# VCO.net
KiCad netlist of a schematic drawn in Altium Designer
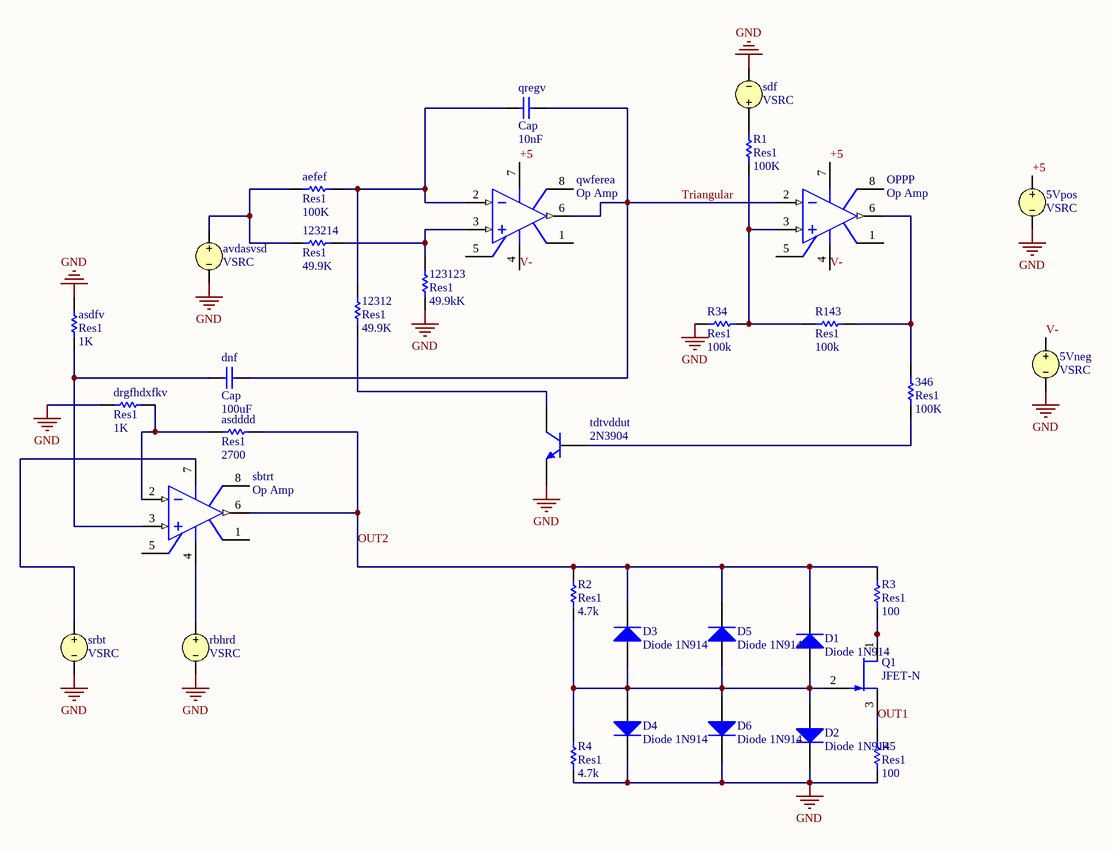
[diagram p0: VCO.SchDoc]

(export (version "E")
  (design (tool "Eeschema 10.0.6"))
  (components
    (comp (ref "5Vneg")
      (value "VSRC")
      (description "Voltage Source")
      (fields (field (name "PUBLISHER") "Altium Limited"))
      (libsource (lib "Simulation Sources") (part "VSRC"))
    )
    (comp (ref "5Vpos")
      (value "VSRC")
      (description "Voltage Source")
      (fields (field (name "PUBLISHER") "Altium Limited"))
      (libsource (lib "Simulation Sources") (part "VSRC"))
    )
    (comp (ref "346")
      (value "Res1")
      (footprint "AXIAL-0.3")
      (description "Resistor")
      (fields (field (name "ALTIUM_VALUE") "100K") (field (name "PUBLISHER") "Altium Limited"))
      (libsource (lib "Miscellaneous Devices") (part "Res1"))
    )
    (comp (ref "12312")
      (value "Res1")
      (footprint "AXIAL-0.3")
      (description "Resistor")
      (fields (field (name "ALTIUM_VALUE") "49.9K") (field (name "PUBLISHER") "Altium Limited"))
      (libsource (lib "Miscellaneous Devices") (part "Res1"))
    )
    (comp (ref "123123")
      (value "Res1")
      (footprint "AXIAL-0.3")
      (description "Resistor")
      (fields (field (name "ALTIUM_VALUE") "49.9kK") (field (name "PUBLISHER") "Altium Limited"))
      (libsource (lib "Miscellaneous Devices") (part "Res1"))
    )
    (comp (ref "123214")
      (value "Res1")
      (footprint "AXIAL-0.3")
      (description "Resistor")
      (fields (field (name "ALTIUM_VALUE") "49.9K") (field (name "PUBLISHER") "Altium Limited"))
      (libsource (lib "Miscellaneous Devices") (part "Res1"))
    )
    (comp (ref "aefef")
      (value "Res1")
      (footprint "AXIAL-0.3")
      (description "Resistor")
      (fields (field (name "ALTIUM_VALUE") "100K") (field (name "PUBLISHER") "Altium Limited"))
      (libsource (lib "Miscellaneous Devices") (part "Res1"))
    )
    (comp (ref "asdddd")
      (value "Res1")
      (footprint "AXIAL-0.3")
      (description "Resistor")
      (fields (field (name "ALTIUM_VALUE") "2700") (field (name "PUBLISHER") "Altium Limited"))
      (libsource (lib "Miscellaneous Devices") (part "Res1"))
    )
    (comp (ref "asdfv")
      (value "Res1")
      (footprint "AXIAL-0.3")
      (description "Resistor")
      (fields (field (name "ALTIUM_VALUE") "1K") (field (name "PUBLISHER") "Altium Limited"))
      (libsource (lib "Miscellaneous Devices") (part "Res1"))
    )
    (comp (ref "avdasvsd")
      (value "VSRC")
      (description "Voltage Source")
      (fields (field (name "PUBLISHER") "Altium Limited"))
      (libsource (lib "Simulation Sources") (part "VSRC"))
    )
    (comp (ref "D1")
      (value "Diode 1N914")
      (footprint "DO-35")
      (description "High Conductance Fast Diode")
      (fields (field (name "PUBLISHER") "Altium Limited"))
      (libsource (lib "Miscellaneous Devices") (part "Diode 1N914"))
    )
    (comp (ref "D2")
      (value "Diode 1N914")
      (footprint "DO-35")
      (description "High Conductance Fast Diode")
      (fields (field (name "PUBLISHER") "Altium Limited"))
      (libsource (lib "Miscellaneous Devices") (part "Diode 1N914"))
    )
    (comp (ref "D3")
      (value "Diode 1N914")
      (footprint "DO-35")
      (description "High Conductance Fast Diode")
      (fields (field (name "PUBLISHER") "Altium Limited"))
      (libsource (lib "Miscellaneous Devices") (part "Diode 1N914"))
    )
    (comp (ref "D4")
      (value "Diode 1N914")
      (footprint "DO-35")
      (description "High Conductance Fast Diode")
      (fields (field (name "PUBLISHER") "Altium Limited"))
      (libsource (lib "Miscellaneous Devices") (part "Diode 1N914"))
    )
    (comp (ref "D5")
      (value "Diode 1N914")
      (footprint "DO-35")
      (description "High Conductance Fast Diode")
      (fields (field (name "PUBLISHER") "Altium Limited"))
      (libsource (lib "Miscellaneous Devices") (part "Diode 1N914"))
    )
    (comp (ref "D6")
      (value "Diode 1N914")
      (footprint "DO-35")
      (description "High Conductance Fast Diode")
      (fields (field (name "PUBLISHER") "Altium Limited"))
      (libsource (lib "Miscellaneous Devices") (part "Diode 1N914"))
    )
    (comp (ref "dnf")
      (value "Cap")
      (footprint "RAD-0.3")
      (description "Capacitor")
      (fields (field (name "ALTIUM_VALUE") "100uF") (field (name "PUBLISHER") "Altium Limited"))
      (libsource (lib "Miscellaneous Devices") (part "Cap"))
    )
    (comp (ref "drgfhdxfkv")
      (value "Res1")
      (footprint "AXIAL-0.3")
      (description "Resistor")
      (fields (field (name "ALTIUM_VALUE") "1K") (field (name "PUBLISHER") "Altium Limited"))
      (libsource (lib "Miscellaneous Devices") (part "Res1"))
    )
    (comp (ref "OPPP")
      (value "Op Amp")
      (footprint "H-08A")
      (description "FET Operational Amplifier")
      (fields (field (name "PUBLISHER") "Altium Limited"))
      (libsource (lib "Miscellaneous Devices") (part "Op Amp"))
    )
    (comp (ref "Q1")
      (value "JFET-N")
      (footprint "TO-254-AA")
      (description "N-Channel JFET")
      (fields (field (name "PUBLISHER") "Altium Limited"))
      (libsource (lib "Miscellaneous Devices") (part "JFET-N"))
    )
    (comp (ref "qregv")
      (value "Cap")
      (footprint "RAD-0.3")
      (description "Capacitor")
      (fields (field (name "ALTIUM_VALUE") "10nF") (field (name "PUBLISHER") "Altium Limited"))
      (libsource (lib "Miscellaneous Devices") (part "Cap"))
    )
    (comp (ref "qwferea")
      (value "Op Amp")
      (footprint "H-08A")
      (description "FET Operational Amplifier")
      (fields (field (name "PUBLISHER") "Altium Limited"))
      (libsource (lib "Miscellaneous Devices") (part "Op Amp"))
    )
    (comp (ref "R1")
      (value "Res1")
      (footprint "AXIAL-0.3")
      (description "Resistor")
      (fields (field (name "ALTIUM_VALUE") "100K") (field (name "PUBLISHER") "Altium Limited"))
      (libsource (lib "Miscellaneous Devices") (part "Res1"))
    )
    (comp (ref "R2")
      (value "Res1")
      (footprint "AXIAL-0.3")
      (description "Resistor")
      (fields (field (name "ALTIUM_VALUE") "4.7k") (field (name "PUBLISHER") "Altium Limited"))
      (libsource (lib "Miscellaneous Devices") (part "Res1"))
    )
    (comp (ref "R3")
      (value "Res1")
      (footprint "AXIAL-0.3")
      (description "Resistor")
      (fields (field (name "ALTIUM_VALUE") "100") (field (name "PUBLISHER") "Altium Limited"))
      (libsource (lib "Miscellaneous Devices") (part "Res1"))
    )
    (comp (ref "R4")
      (value "Res1")
      (footprint "AXIAL-0.3")
      (description "Resistor")
      (fields (field (name "ALTIUM_VALUE") "4.7k") (field (name "PUBLISHER") "Altium Limited"))
      (libsource (lib "Miscellaneous Devices") (part "Res1"))
    )
    (comp (ref "R5")
      (value "Res1")
      (footprint "AXIAL-0.3")
      (description "Resistor")
      (fields (field (name "ALTIUM_VALUE") "100") (field (name "PUBLISHER") "Altium Limited"))
      (libsource (lib "Miscellaneous Devices") (part "Res1"))
    )
    (comp (ref "R34")
      (value "Res1")
      (footprint "AXIAL-0.3")
      (description "Resistor")
      (fields (field (name "ALTIUM_VALUE") "100k") (field (name "PUBLISHER") "Altium Limited"))
      (libsource (lib "Miscellaneous Devices") (part "Res1"))
    )
    (comp (ref "R143")
      (value "Res1")
      (footprint "AXIAL-0.3")
      (description "Resistor")
      (fields (field (name "ALTIUM_VALUE") "100k") (field (name "PUBLISHER") "Altium Limited"))
      (libsource (lib "Miscellaneous Devices") (part "Res1"))
    )
    (comp (ref "rbhrd")
      (value "VSRC")
      (description "Voltage Source")
      (fields (field (name "PUBLISHER") "Altium Limited"))
      (libsource (lib "Simulation Sources") (part "VSRC"))
    )
    (comp (ref "sbtrt")
      (value "Op Amp")
      (footprint "H-08A")
      (description "FET Operational Amplifier")
      (fields (field (name "PUBLISHER") "Altium Limited"))
      (libsource (lib "Miscellaneous Devices") (part "Op Amp"))
    )
    (comp (ref "sdf")
      (value "VSRC")
      (description "Voltage Source")
      (fields (field (name "PUBLISHER") "Altium Limited"))
      (libsource (lib "Simulation Sources") (part "VSRC"))
    )
    (comp (ref "srbt")
      (value "VSRC")
      (description "Voltage Source")
      (fields (field (name "PUBLISHER") "Altium Limited"))
      (libsource (lib "Simulation Sources") (part "VSRC"))
    )
    (comp (ref "tdtvddut")
      (value "2N3904")
      (footprint "TO-92A")
      (description "NPN General Purpose Amplifier")
      (fields (field (name "PUBLISHER") "Altium Limited"))
      (libsource (lib "Miscellaneous Devices") (part "2N3904"))
    )
  )
  (nets
    (net (code "1") (name "/+5") (class "Default")
      (node (ref "5Vpos") (pin "1") (pinfunction "1_1") (pintype "passive"))
      (node (ref "OPPP") (pin "7") (pinfunction "V+_7") (pintype "power_in"))
      (node (ref "qwferea") (pin "7") (pinfunction "V+_7") (pintype "power_in"))
    )
    (net (code "2") (name "/OUT1") (class "Default")
      (node (ref "Q1") (pin "3") (pinfunction "S_3") (pintype "passive"))
      (node (ref "R5") (pin "2") (pinfunction "2_2") (pintype "passive"))
    )
    (net (code "3") (name "/OUT2") (class "Default")
      (node (ref "D1") (pin "2") (pinfunction "K_2") (pintype "passive"))
      (node (ref "D3") (pin "2") (pinfunction "K_2") (pintype "passive"))
      (node (ref "D5") (pin "2") (pinfunction "K_2") (pintype "passive"))
      (node (ref "R2") (pin "2") (pinfunction "2_2") (pintype "passive"))
      (node (ref "R3") (pin "2") (pinfunction "2_2") (pintype "passive"))
      (node (ref "asdddd") (pin "2") (pinfunction "2_2") (pintype "passive"))
      (node (ref "sbtrt") (pin "6") (pinfunction "OUT_6") (pintype "output"))
    )
    (net (code "4") (name "/Triangular") (class "Default")
      (node (ref "OPPP") (pin "2") (pinfunction "IN-_2") (pintype "input"))
      (node (ref "dnf") (pin "2") (pinfunction "2_2") (pintype "passive"))
      (node (ref "qregv") (pin "2") (pinfunction "2_2") (pintype "passive"))
      (node (ref "qwferea") (pin "6") (pinfunction "OUT_6") (pintype "output"))
    )
    (net (code "5") (name "/V-") (class "Default")
      (node (ref "5Vneg") (pin "1") (pinfunction "1_1") (pintype "passive"))
      (node (ref "OPPP") (pin "4") (pinfunction "V-_4") (pintype "power_in"))
      (node (ref "qwferea") (pin "4") (pinfunction "V-_4") (pintype "power_in"))
    )
    (net (code "6") (name "GND") (class "Default")
      (node (ref "123123") (pin "1") (pinfunction "1_1") (pintype "passive"))
      (node (ref "5Vneg") (pin "2") (pinfunction "2_2") (pintype "passive"))
      (node (ref "5Vpos") (pin "2") (pinfunction "2_2") (pintype "passive"))
      (node (ref "D2") (pin "2") (pinfunction "K_2") (pintype "passive"))
      (node (ref "D4") (pin "2") (pinfunction "K_2") (pintype "passive"))
      (node (ref "D6") (pin "2") (pinfunction "K_2") (pintype "passive"))
      (node (ref "R34") (pin "1") (pinfunction "1_1") (pintype "passive"))
      (node (ref "R4") (pin "1") (pinfunction "1_1") (pintype "passive"))
      (node (ref "R5") (pin "1") (pinfunction "1_1") (pintype "passive"))
      (node (ref "asdfv") (pin "2") (pinfunction "2_2") (pintype "passive"))
      (node (ref "avdasvsd") (pin "2") (pinfunction "2_2") (pintype "passive"))
      (node (ref "drgfhdxfkv") (pin "2") (pinfunction "2_2") (pintype "passive"))
      (node (ref "rbhrd") (pin "2") (pinfunction "2_2") (pintype "passive"))
      (node (ref "sdf") (pin "2") (pinfunction "2_2") (pintype "passive"))
      (node (ref "srbt") (pin "2") (pinfunction "2_2") (pintype "passive"))
      (node (ref "tdtvddut") (pin "1") (pinfunction "E_1") (pintype "passive"))
    )
    (net (code "7") (name "Net-(123214-Pad1)") (class "Default")
      (node (ref "123214") (pin "1") (pinfunction "1_1") (pintype "passive"))
      (node (ref "aefef") (pin "1") (pinfunction "1_1") (pintype "passive"))
      (node (ref "avdasvsd") (pin "1") (pinfunction "1_1") (pintype "passive"))
    )
    (net (code "8") (name "Net-(D1-A)") (class "Default")
      (node (ref "D1") (pin "1") (pinfunction "A_1") (pintype "passive"))
      (node (ref "D2") (pin "1") (pinfunction "A_1") (pintype "passive"))
      (node (ref "D3") (pin "1") (pinfunction "A_1") (pintype "passive"))
      (node (ref "D4") (pin "1") (pinfunction "A_1") (pintype "passive"))
      (node (ref "D5") (pin "1") (pinfunction "A_1") (pintype "passive"))
      (node (ref "D6") (pin "1") (pinfunction "A_1") (pintype "passive"))
      (node (ref "Q1") (pin "2") (pinfunction "G_2") (pintype "passive"))
      (node (ref "R2") (pin "1") (pinfunction "1_1") (pintype "passive"))
      (node (ref "R4") (pin "2") (pinfunction "2_2") (pintype "passive"))
    )
    (net (code "9") (name "Net-(OPPP-IN+)") (class "Default")
      (node (ref "OPPP") (pin "3") (pinfunction "IN+_3") (pintype "input"))
      (node (ref "R1") (pin "1") (pinfunction "1_1") (pintype "passive"))
      (node (ref "R143") (pin "1") (pinfunction "1_1") (pintype "passive"))
      (node (ref "R34") (pin "2") (pinfunction "2_2") (pintype "passive"))
    )
    (net (code "10") (name "Net-(OPPP-OUT)") (class "Default")
      (node (ref "346") (pin "2") (pinfunction "2_2") (pintype "passive"))
      (node (ref "OPPP") (pin "6") (pinfunction "OUT_6") (pintype "output"))
      (node (ref "R143") (pin "2") (pinfunction "2_2") (pintype "passive"))
    )
    (net (code "11") (name "Net-(Q1-D)") (class "Default")
      (node (ref "Q1") (pin "1") (pinfunction "D_1") (pintype "passive"))
      (node (ref "R3") (pin "1") (pinfunction "1_1") (pintype "passive"))
    )
    (net (code "12") (name "Net-(R1-Pad2)") (class "Default")
      (node (ref "R1") (pin "2") (pinfunction "2_2") (pintype "passive"))
      (node (ref "sdf") (pin "1") (pinfunction "1_1") (pintype "passive"))
    )
    (net (code "13") (name "Net-(qwferea-IN+)") (class "Default")
      (node (ref "123123") (pin "2") (pinfunction "2_2") (pintype "passive"))
      (node (ref "123214") (pin "2") (pinfunction "2_2") (pintype "passive"))
      (node (ref "qwferea") (pin "3") (pinfunction "IN+_3") (pintype "input"))
    )
    (net (code "14") (name "Net-(qwferea-IN-)") (class "Default")
      (node (ref "12312") (pin "2") (pinfunction "2_2") (pintype "passive"))
      (node (ref "aefef") (pin "2") (pinfunction "2_2") (pintype "passive"))
      (node (ref "qregv") (pin "1") (pinfunction "1_1") (pintype "passive"))
      (node (ref "qwferea") (pin "2") (pinfunction "IN-_2") (pintype "input"))
    )
    (net (code "15") (name "Net-(sbtrt-IN+)") (class "Default")
      (node (ref "asdfv") (pin "1") (pinfunction "1_1") (pintype "passive"))
      (node (ref "dnf") (pin "1") (pinfunction "1_1") (pintype "passive"))
      (node (ref "sbtrt") (pin "3") (pinfunction "IN+_3") (pintype "input"))
    )
    (net (code "16") (name "Net-(sbtrt-IN-)") (class "Default")
      (node (ref "asdddd") (pin "1") (pinfunction "1_1") (pintype "passive"))
      (node (ref "drgfhdxfkv") (pin "1") (pinfunction "1_1") (pintype "passive"))
      (node (ref "sbtrt") (pin "2") (pinfunction "IN-_2") (pintype "input"))
    )
    (net (code "17") (name "Net-(sbtrt-V+)") (class "Default")
      (node (ref "sbtrt") (pin "7") (pinfunction "V+_7") (pintype "power_in"))
      (node (ref "srbt") (pin "1") (pinfunction "1_1") (pintype "passive"))
    )
    (net (code "18") (name "Net-(sbtrt-V-)") (class "Default")
      (node (ref "rbhrd") (pin "1") (pinfunction "1_1") (pintype "passive"))
      (node (ref "sbtrt") (pin "4") (pinfunction "V-_4") (pintype "power_in"))
    )
    (net (code "19") (name "Net-(tdtvddut-B)") (class "Default")
      (node (ref "346") (pin "1") (pinfunction "1_1") (pintype "passive"))
      (node (ref "tdtvddut") (pin "2") (pinfunction "B_2") (pintype "passive"))
    )
    (net (code "20") (name "Net-(tdtvddut-C)") (class "Default")
      (node (ref "12312") (pin "1") (pinfunction "1_1") (pintype "passive"))
      (node (ref "tdtvddut") (pin "3") (pinfunction "C_3") (pintype "passive"))
    )
    (net (code "21") (name "unconnected-(OPPP-OS_NUL-Pad1)") (class "Default")
      (node (ref "OPPP") (pin "1") (pinfunction "OS_NUL_1") (pintype "passive"))
    )
    (net (code "22") (name "unconnected-(OPPP-OS_NUL-Pad5)") (class "Default")
      (node (ref "OPPP") (pin "5") (pinfunction "OS_NUL_5") (pintype "passive"))
    )
    (net (code "23") (name "unconnected-(OPPP-TAB-Pad8)") (class "Default")
      (node (ref "OPPP") (pin "8") (pinfunction "TAB_8") (pintype "passive"))
    )
    (net (code "24") (name "unconnected-(qwferea-OS_NUL-Pad1)") (class "Default")
      (node (ref "qwferea") (pin "1") (pinfunction "OS_NUL_1") (pintype "passive"))
    )
    (net (code "25") (name "unconnected-(qwferea-OS_NUL-Pad5)") (class "Default")
      (node (ref "qwferea") (pin "5") (pinfunction "OS_NUL_5") (pintype "passive"))
    )
    (net (code "26") (name "unconnected-(qwferea-TAB-Pad8)") (class "Default")
      (node (ref "qwferea") (pin "8") (pinfunction "TAB_8") (pintype "passive"))
    )
    (net (code "27") (name "unconnected-(sbtrt-OS_NUL-Pad1)") (class "Default")
      (node (ref "sbtrt") (pin "1") (pinfunction "OS_NUL_1") (pintype "passive"))
    )
    (net (code "28") (name "unconnected-(sbtrt-OS_NUL-Pad5)") (class "Default")
      (node (ref "sbtrt") (pin "5") (pinfunction "OS_NUL_5") (pintype "passive"))
    )
    (net (code "29") (name "unconnected-(sbtrt-TAB-Pad8)") (class "Default")
      (node (ref "sbtrt") (pin "8") (pinfunction "TAB_8") (pintype "passive"))
    )
  )
)
